# Glog_5G_V1.net
KiCad netlist of a schematic drawn in Altium Designer
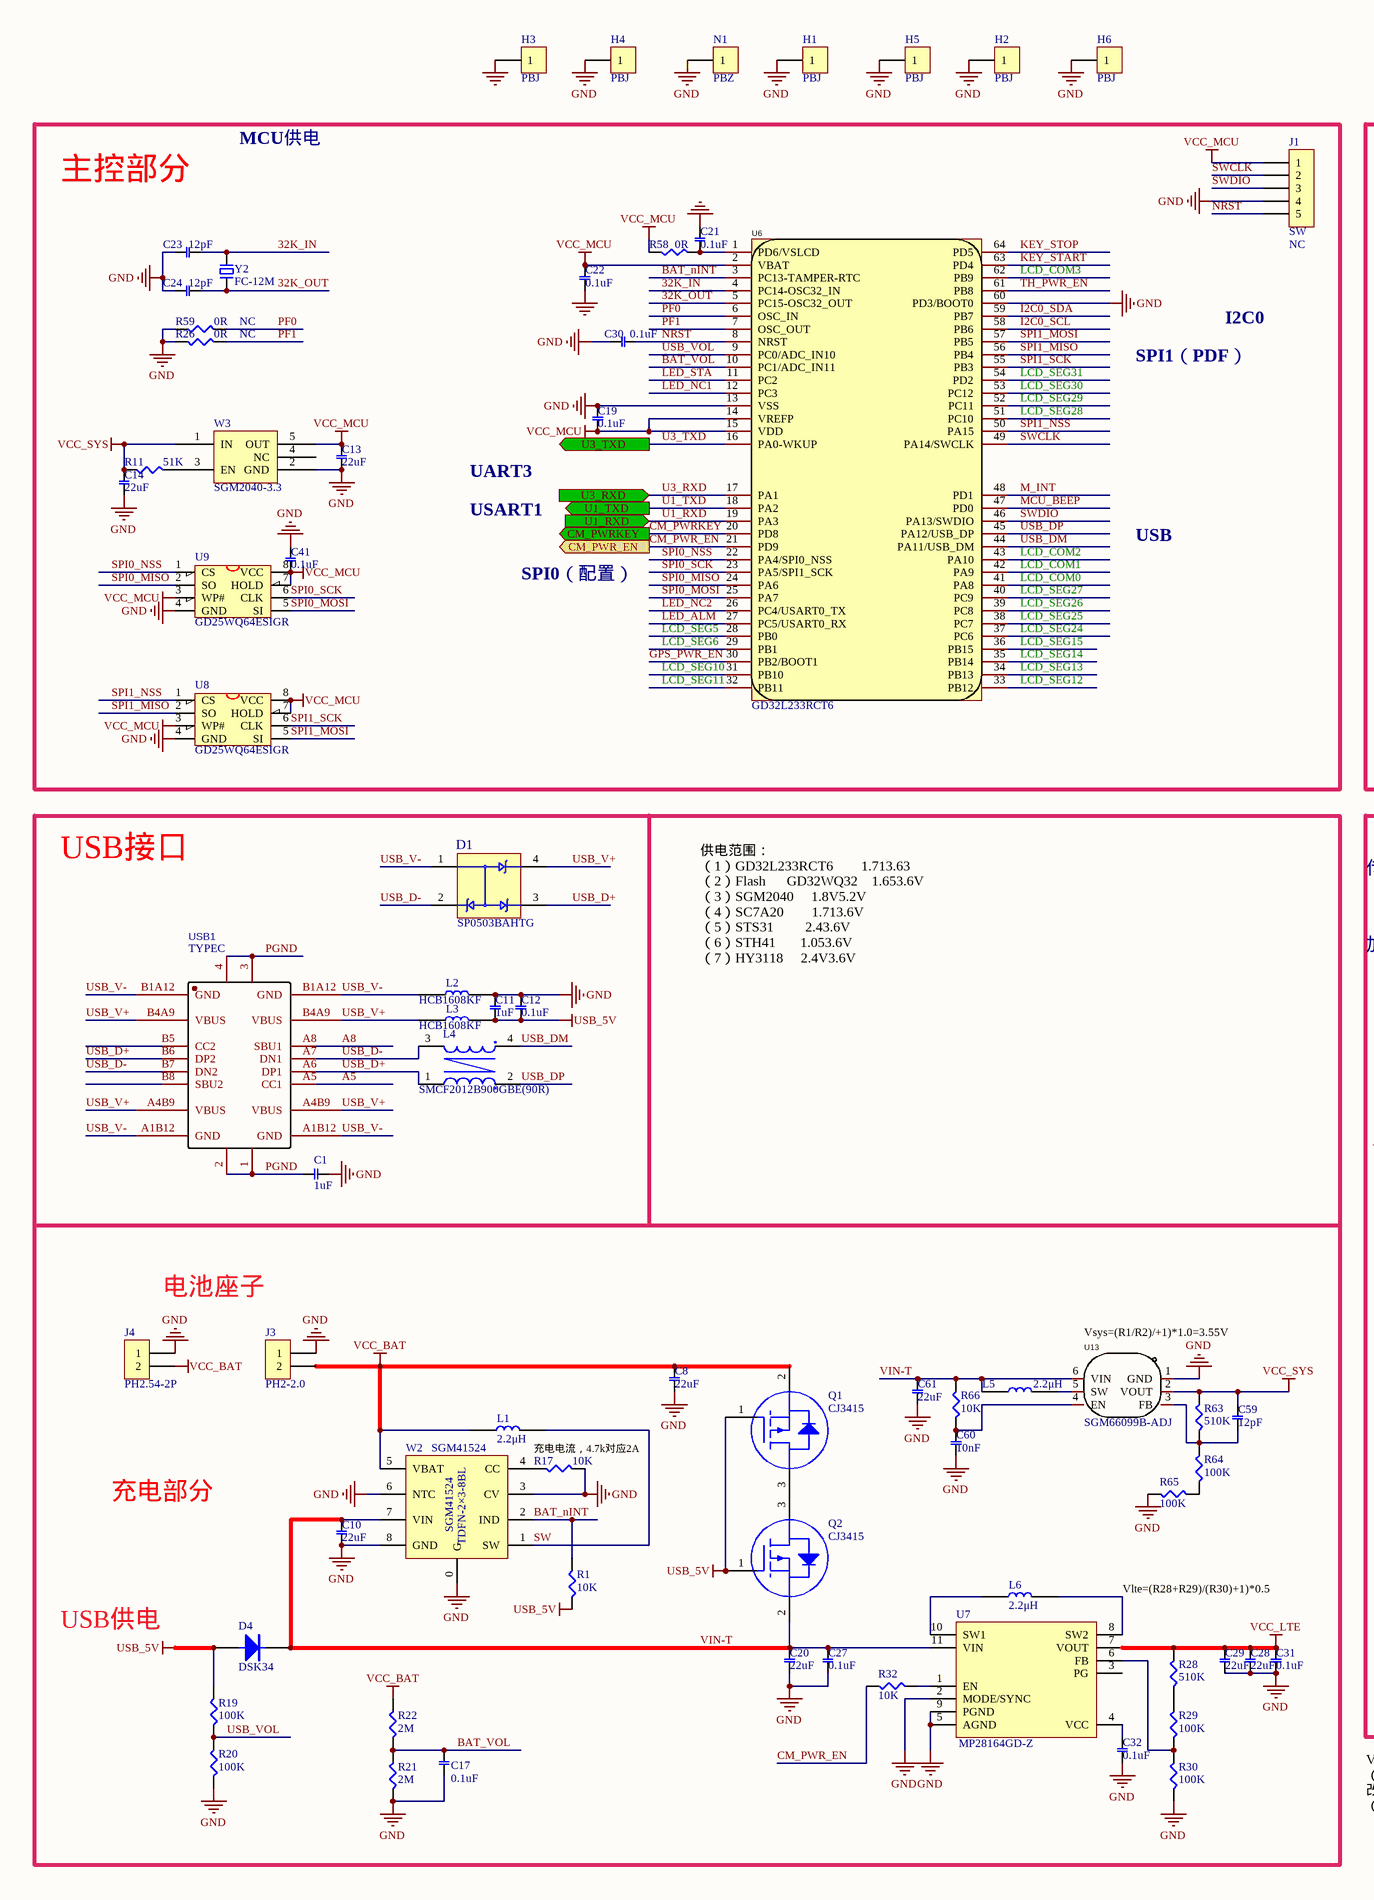
[diagram p0: Glog 5G_V1.SchDoc, left]
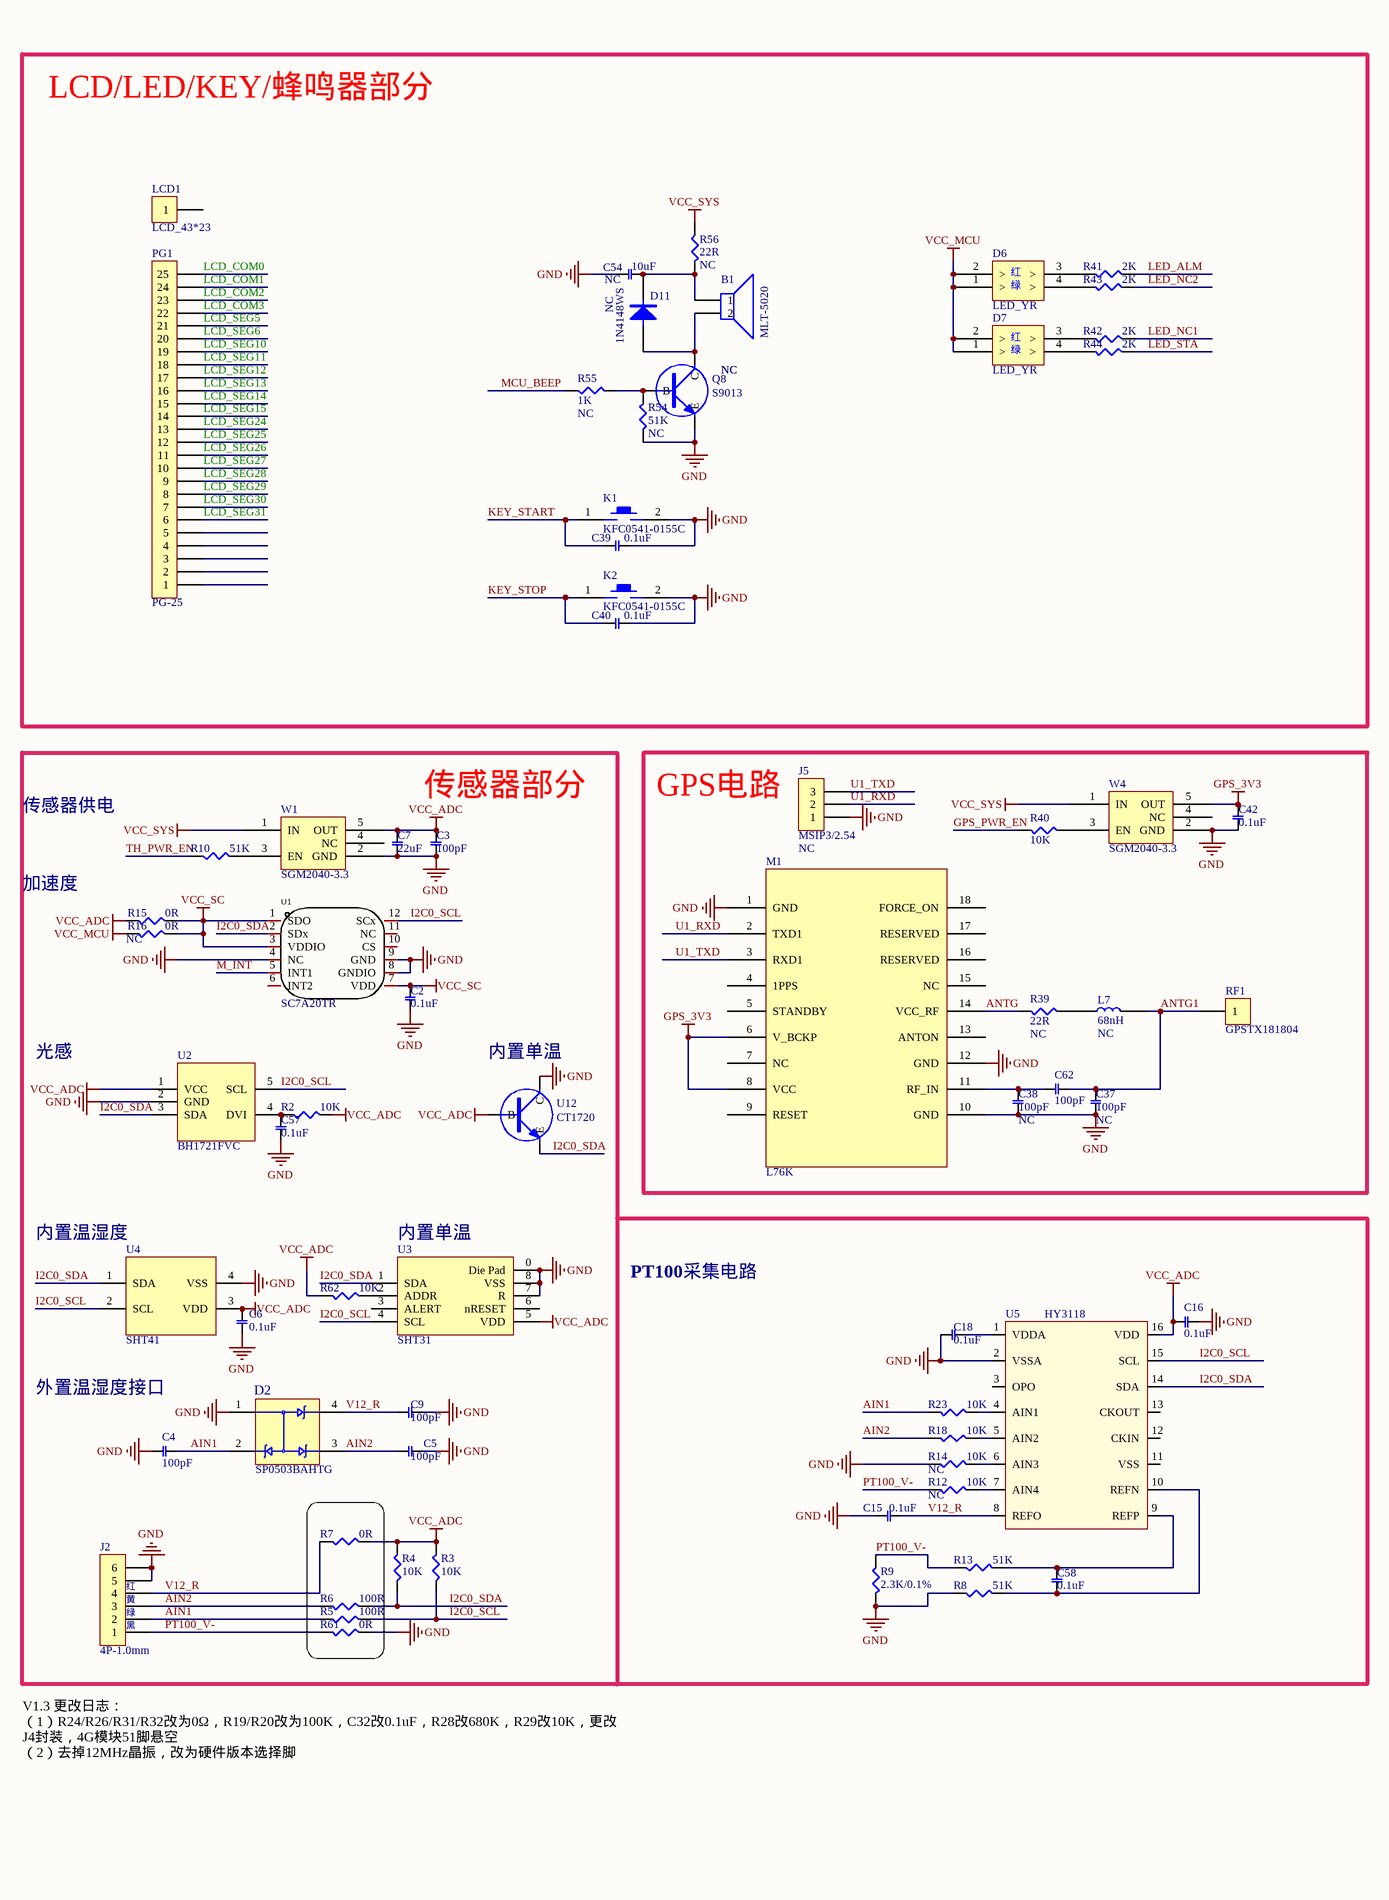
[diagram p1: Glog 5G_V1.SchDoc, right]

(export (version "E")
  (design (tool "Eeschema 10.0.6"))
  (components
    (comp (ref "B1")
      (value "MLT-5020")
      (footprint "MLT-5225")
      (fields (field (name "VALUES") "MLT-5020") (field (name "选焊") "NC"))
      (libsource (lib "JC_ERP_DB") (part "BUZZ"))
    )
    (comp (ref "C1")
      (value "1uF")
      (footprint "0402C")
      (fields (field (name "VALUES") "1uF"))
      (libsource (lib "JC_ERP_DB") (part "Capacity-CE"))
    )
    (comp (ref "C2")
      (value "0.1uF")
      (footprint "0402C")
      (fields (field (name "VALUES") "0.1uF"))
      (libsource (lib "JC_ERP_DB") (part "Capacity-CE"))
    )
    (comp (ref "C3")
      (value "100pF")
      (footprint "0402C")
      (fields (field (name "VALUES") "100pF"))
      (libsource (lib "JC_ERP_DB") (part "Capacity-CE"))
    )
    (comp (ref "C4")
      (value "100pF")
      (footprint "0402C")
      (fields (field (name "VALUES") "100pF"))
      (libsource (lib "JC_ERP_DB") (part "Capacity-CE"))
    )
    (comp (ref "C5")
      (value "100pF")
      (footprint "0402C")
      (fields (field (name "VALUES") "100pF"))
      (libsource (lib "JC_ERP_DB") (part "Capacity-CE"))
    )
    (comp (ref "C6")
      (value "0.1uF")
      (footprint "0402C")
      (fields (field (name "VALUES") "0.1uF"))
      (libsource (lib "JC_ERP_DB") (part "Capacity-CE"))
    )
    (comp (ref "C7")
      (value "22uF")
      (footprint "0603C")
      (fields (field (name "VALUES") "22uF"))
      (libsource (lib "JC_ERP_DB") (part "Capacity-CE"))
    )
    (comp (ref "C8")
      (value "22uF")
      (footprint "0603C")
      (fields (field (name "VALUES") "22uF"))
      (libsource (lib "JC_ERP_DB") (part "Capacity-CE"))
    )
    (comp (ref "C9")
      (value "100pF")
      (footprint "0402C")
      (fields (field (name "VALUES") "100pF"))
      (libsource (lib "JC_ERP_DB") (part "Capacity-CE"))
    )
    (comp (ref "C10")
      (value "22uF")
      (footprint "0603C")
      (fields (field (name "VALUES") "22uF"))
      (libsource (lib "JC_ERP_DB") (part "Capacity-CE"))
    )
    (comp (ref "C11")
      (value "1uF")
      (footprint "0402C")
      (fields (field (name "VALUES") "1uF"))
      (libsource (lib "JC_ERP_DB") (part "Capacity-CE"))
    )
    (comp (ref "C12")
      (value "0.1uF")
      (footprint "0402C")
      (fields (field (name "VALUES") "0.1uF"))
      (libsource (lib "JC_ERP_DB") (part "Capacity-CE"))
    )
    (comp (ref "C13")
      (value "22uF")
      (footprint "0603C")
      (fields (field (name "VALUES") "22uF"))
      (libsource (lib "JC_ERP_DB") (part "Capacity-CE"))
    )
    (comp (ref "C14")
      (value "22uF")
      (footprint "0603C")
      (fields (field (name "VALUES") "22uF"))
      (libsource (lib "JC_ERP_DB") (part "Capacity-CE"))
    )
    (comp (ref "C15")
      (value "0.1uF")
      (footprint "0402C")
      (fields (field (name "VALUES") "0.1uF"))
      (libsource (lib "JC_ERP_DB") (part "Capacity-CE"))
    )
    (comp (ref "C16")
      (value "0.1uF")
      (footprint "0402C")
      (fields (field (name "VALUES") "0.1uF"))
      (libsource (lib "JC_ERP_DB") (part "Capacity-CE"))
    )
    (comp (ref "C17")
      (value "0.1uF")
      (footprint "0402C")
      (fields (field (name "VALUES") "0.1uF"))
      (libsource (lib "JC_ERP_DB") (part "Capacity-CE"))
    )
    (comp (ref "C18")
      (value "0.1uF")
      (footprint "0402C")
      (fields (field (name "VALUES") "0.1uF"))
      (libsource (lib "JC_ERP_DB") (part "Capacity-CE"))
    )
    (comp (ref "C19")
      (value "0.1uF")
      (footprint "0402C")
      (fields (field (name "VALUES") "0.1uF"))
      (libsource (lib "JC_ERP_DB") (part "Capacity-CE"))
    )
    (comp (ref "C20")
      (value "22uF")
      (footprint "0603C")
      (fields (field (name "VALUES") "22uF"))
      (libsource (lib "JC_ERP_DB") (part "Capacity-CE"))
    )
    (comp (ref "C21")
      (value "0.1uF")
      (footprint "0402C")
      (fields (field (name "VALUES") "0.1uF"))
      (libsource (lib "JC_ERP_DB") (part "Capacity-CE"))
    )
    (comp (ref "C22")
      (value "0.1uF")
      (footprint "0402C")
      (fields (field (name "VALUES") "0.1uF"))
      (libsource (lib "JC_ERP_DB") (part "Capacity-CE"))
    )
    (comp (ref "C23")
      (value "12pF")
      (footprint "0402C")
      (fields (field (name "VALUES") "12pF"))
      (libsource (lib "JC_ERP_DB") (part "Capacity-CE"))
    )
    (comp (ref "C24")
      (value "12pF")
      (footprint "0402C")
      (fields (field (name "VALUES") "12pF"))
      (libsource (lib "JC_ERP_DB") (part "Capacity-CE"))
    )
    (comp (ref "C27")
      (value "0.1uF")
      (footprint "0402C")
      (fields (field (name "VALUES") "0.1uF"))
      (libsource (lib "JC_ERP_DB") (part "Capacity-CE"))
    )
    (comp (ref "C28")
      (value "22uF")
      (footprint "0603C")
      (fields (field (name "VALUES") "22uF"))
      (libsource (lib "JC_ERP_DB") (part "Capacity-CE"))
    )
    (comp (ref "C29")
      (value "22uF")
      (footprint "0603C")
      (fields (field (name "VALUES") "22uF"))
      (libsource (lib "JC_ERP_DB") (part "Capacity-CE"))
    )
    (comp (ref "C30")
      (value "0.1uF")
      (footprint "0402C")
      (fields (field (name "VALUES") "0.1uF"))
      (libsource (lib "JC_ERP_DB") (part "Capacity-CE"))
    )
    (comp (ref "C31")
      (value "0.1uF")
      (footprint "0402C")
      (fields (field (name "VALUES") "0.1uF"))
      (libsource (lib "JC_ERP_DB") (part "Capacity-CE"))
    )
    (comp (ref "C32")
      (value "0.1uF")
      (footprint "0402C")
      (fields (field (name "VALUES") "0.1uF"))
      (libsource (lib "JC_ERP_DB") (part "Capacity-CE"))
    )
    (comp (ref "C37")
      (value "100pF")
      (footprint "0402C")
      (fields (field (name "VALUES") "100pF") (field (name "选焊") "NC"))
      (libsource (lib "JC_ERP_DB") (part "Capacity-CE"))
    )
    (comp (ref "C38")
      (value "100pF")
      (footprint "0402C")
      (fields (field (name "VALUES") "100pF") (field (name "选焊") "NC"))
      (libsource (lib "JC_ERP_DB") (part "Capacity-CE"))
    )
    (comp (ref "C39")
      (value "0.1uF")
      (footprint "0402C")
      (fields (field (name "VALUES") "0.1uF"))
      (libsource (lib "JC_ERP_DB") (part "Capacity-CE"))
    )
    (comp (ref "C40")
      (value "0.1uF")
      (footprint "0402C")
      (fields (field (name "VALUES") "0.1uF"))
      (libsource (lib "JC_ERP_DB") (part "Capacity-CE"))
    )
    (comp (ref "C41")
      (value "0.1uF")
      (footprint "0402C")
      (fields (field (name "VALUES") "0.1uF"))
      (libsource (lib "JC_ERP_DB") (part "Capacity-CE"))
    )
    (comp (ref "C42")
      (value "0.1uF")
      (footprint "0402C")
      (fields (field (name "VALUES") "0.1uF"))
      (libsource (lib "JC_ERP_DB") (part "Capacity-CE"))
    )
    (comp (ref "C54")
      (value "10uF")
      (footprint "0603C")
      (fields (field (name "VALUES") "10uF") (field (name "选焊") "NC"))
      (libsource (lib "JC_ERP_DB") (part "Capacity-CE"))
    )
    (comp (ref "C57")
      (value "0.1uF")
      (footprint "0402C")
      (fields (field (name "VALUES") "0.1uF"))
      (libsource (lib "JC_ERP_DB") (part "Capacity-CE"))
    )
    (comp (ref "C58")
      (value "0.1uF")
      (footprint "0402C")
      (fields (field (name "VALUES") "0.1uF"))
      (libsource (lib "JC_ERP_DB") (part "Capacity-CE"))
    )
    (comp (ref "C59")
      (value "12pF")
      (footprint "0402C")
      (fields (field (name "VALUES") "12pF"))
      (libsource (lib "JC_ERP_DB") (part "Capacity-CE"))
    )
    (comp (ref "C60")
      (value "10nF")
      (footprint "0402C")
      (fields (field (name "VALUES") "10nF"))
      (libsource (lib "JC_ERP_DB") (part "Capacity-CE"))
    )
    (comp (ref "C61")
      (value "22uF")
      (footprint "0603C")
      (fields (field (name "VALUES") "22uF"))
      (libsource (lib "JC_ERP_DB") (part "Capacity-CE"))
    )
    (comp (ref "C62")
      (value "100pF")
      (footprint "0402C")
      (fields (field (name "VALUES") "100pF"))
      (libsource (lib "JC_ERP_DB") (part "Capacity-CE"))
    )
    (comp (ref "D1")
      (value "SP0503BAHTG")
      (footprint "SP0503")
      (fields (field (name "VALUES") "SP0503BAHTG"))
      (libsource (lib "JC_ERP_DB") (part "SP0503BATH"))
    )
    (comp (ref "D2")
      (value "SP0503BAHTG")
      (footprint "SP0503")
      (fields (field (name "VALUES") "SP0503BAHTG"))
      (libsource (lib "JC_ERP_DB") (part "SP0503BATH"))
    )
    (comp (ref "D4")
      (value "DSK34")
      (footprint "SOD-123FL")
      (fields (field (name "VALUES") "DSK34"))
      (libsource (lib "JC_ERP_DB") (part "Diode"))
    )
    (comp (ref "D6")
      (value "LED_YR")
      (footprint "TWO_LED_2COL_0805")
      (fields (field (name "VALUES") "LED_YR"))
      (libsource (lib "JC_ERP_DB") (part "0805-D-LED"))
    )
    (comp (ref "D7")
      (value "LED_YR")
      (footprint "TWO_LED_2COL_0805")
      (fields (field (name "VALUES") "LED_YR"))
      (libsource (lib "JC_ERP_DB") (part "0805-D-LED"))
    )
    (comp (ref "D11")
      (value "1N4148WS")
      (footprint "SOD123")
      (fields (field (name "VALUES") "1N4148WS") (field (name "选焊") "NC"))
      (libsource (lib "JC_ERP_DB") (part "Diode"))
    )
    (comp (ref "H1")
      (value "PBJ")
      (footprint "PBZJZ")
      (fields (field (name "VALUES") "PBJ"))
      (libsource (lib "JC_ERP_DB") (part "CON1P"))
    )
    (comp (ref "H2")
      (value "PBJ")
      (footprint "PBZJZ")
      (fields (field (name "VALUES") "PBJ"))
      (libsource (lib "JC_ERP_DB") (part "CON1P"))
    )
    (comp (ref "H3")
      (value "PBJ")
      (footprint "PBZJZ")
      (fields (field (name "VALUES") "PBJ"))
      (libsource (lib "JC_ERP_DB") (part "CON1P"))
    )
    (comp (ref "H4")
      (value "PBJ")
      (footprint "PBZJZ")
      (fields (field (name "VALUES") "PBJ"))
      (libsource (lib "JC_ERP_DB") (part "CON1P"))
    )
    (comp (ref "H5")
      (value "PBJ")
      (footprint "PBZJZ")
      (fields (field (name "VALUES") "PBJ"))
      (libsource (lib "JC_ERP_DB") (part "CON1P"))
    )
    (comp (ref "H6")
      (value "PBJ")
      (footprint "PBZJZ")
      (fields (field (name "VALUES") "PBJ"))
      (libsource (lib "JC_ERP_DB") (part "CON1P"))
    )
    (comp (ref "J1")
      (value "SW")
      (footprint "HDR1X5")
      (description "Connector")
      (fields (field (name "选焊") "NC"))
      (libsource (lib "Integrated Devices") (part "CON5"))
    )
    (comp (ref "J2")
      (value "4P-1.0mm")
      (footprint "SH1.0MM-4P")
      (fields (field (name "VALUES") "4P-1.0mm"))
      (libsource (lib "JC_ERP_DB") (part "CON-1*6PIN"))
    )
    (comp (ref "J3")
      (value "PH2-2.0")
      (footprint "smd2 dh2")
      (fields (field (name "VALUES") "PH2-2.0"))
      (libsource (lib "JC_ERP_DB") (part "CON-1*2PIN"))
    )
    (comp (ref "J4")
      (value "PH2.54-2P")
      (footprint "SMD_DH2.54_L")
      (fields (field (name "VALUES") "PH2.54-2P"))
      (libsource (lib "JC_ERP_DB") (part "CON-1*2PIN"))
    )
    (comp (ref "J5")
      (value "MSIP3/2.54")
      (footprint "SIP-3(2.54MM)")
      (fields (field (name "VALUES") "MSIP3/2.54") (field (name "选焊") "NC"))
      (libsource (lib "ERP_DB") (part "CON-1*3PIN"))
    )
    (comp (ref "K1")
      (value "KFC0541-0155C")
      (footprint "KEY-0505")
      (fields (field (name "VALUES") "KFC0541-0155C"))
      (libsource (lib "JC_ERP_DB") (part "KEY_M"))
    )
    (comp (ref "K2")
      (value "KFC0541-0155C")
      (footprint "KEY-0505")
      (fields (field (name "VALUES") "KFC0541-0155C"))
      (libsource (lib "JC_ERP_DB") (part "KEY_M"))
    )
    (comp (ref "L1")
      (value "2.2μH")
      (footprint "SMD-4020")
      (fields (field (name "VALUES") "2.2μH"))
      (libsource (lib "JC_ERP_DB") (part "Inductor-SMT-2PIN"))
    )
    (comp (ref "L2")
      (value "HCB1608KF")
      (footprint "0805L")
      (fields (field (name "VALUES") "HCB1608KF"))
      (libsource (lib "JC_ERP_DB") (part "Inductor-SMT-2PIN"))
    )
    (comp (ref "L3")
      (value "HCB1608KF")
      (footprint "0805L")
      (fields (field (name "VALUES") "HCB1608KF"))
      (libsource (lib "JC_ERP_DB") (part "Inductor-SMT-2PIN"))
    )
    (comp (ref "L4")
      (value "SMCF2012B900GBE(90R)")
      (footprint "SMCF2012")
      (fields (field (name "VALUES") "SMCF2012B900GBE(90R)"))
      (libsource (lib "JC_ERP_DB") (part "Inductor-CM"))
    )
    (comp (ref "L5")
      (value "2.2μH")
      (footprint "SMD-4020")
      (fields (field (name "VALUES") "2.2μH"))
      (libsource (lib "JC_ERP_DB") (part "Inductor-SMT-2PIN"))
    )
    (comp (ref "L6")
      (value "2.2μH")
      (footprint "SMD-4020")
      (fields (field (name "VALUES") "2.2μH"))
      (libsource (lib "JC_ERP_DB") (part "Inductor-SMT-2PIN"))
    )
    (comp (ref "L7")
      (value "68nH")
      (footprint "0603L")
      (fields (field (name "VALUES") "68nH") (field (name "选焊") "NC"))
      (libsource (lib "JC_ERP_DB") (part "Inductor-SMT-2PIN"))
    )
    (comp (ref "LCD1")
      (value "LCD_43*23")
      (footprint "LCD_43*23*2.8")
      (fields (field (name "VALUES") "LCD_43*23"))
      (libsource (lib "") (part "CON1P_1"))
    )
    (comp (ref "M1")
      (value "L76K")
      (footprint "L76CGPS")
      (fields (field (name "VALUES") "L76K"))
      (libsource (lib "JC_ERP_DB") (part "L76CGPS"))
    )
    (comp (ref "N1")
      (value "PBZ")
      (footprint "PBZ_36*28mm")
      (fields (field (name "VALUES") "PBZ"))
      (libsource (lib "JC_ERP_DB") (part "CON1P"))
    )
    (comp (ref "PG1")
      (value "PG-25")
      (footprint "PG25-L46*W2*H3mm")
      (fields (field (name "VALUES") "PG-25"))
      (libsource (lib "JC_ERP_DB") (part "CON-1*25PIN"))
    )
    (comp (ref "Q1")
      (value "CJ3415")
      (footprint "SOT-23-MOS")
      (fields (field (name "VALUES") "CJ3415"))
      (libsource (lib "") (part "MOS-P-Z_1"))
    )
    (comp (ref "Q2")
      (value "CJ3415")
      (footprint "SOT-23-MOS")
      (fields (field (name "VALUES") "CJ3415"))
      (libsource (lib "JC_ERP_DB") (part "MOS-P-Z"))
    )
    (comp (ref "Q8")
      (value "S9013")
      (footprint "SOT23-N")
      (fields (field (name "VALUES") "S9013") (field (name "选焊") "NC"))
      (libsource (lib "JC_ERP_DB") (part "Dynatron-NPN"))
    )
    (comp (ref "R1")
      (value "10K")
      (footprint "0402R")
      (fields (field (name "VALUES") "10K"))
      (libsource (lib "JC_ERP_DB") (part "Resistors-SMT"))
    )
    (comp (ref "R2")
      (value "10K")
      (footprint "0402R")
      (fields (field (name "VALUES") "10K"))
      (libsource (lib "JC_ERP_DB") (part "Resistors-SMT"))
    )
    (comp (ref "R3")
      (value "10K")
      (footprint "0402R")
      (fields (field (name "VALUES") "10K"))
      (libsource (lib "JC_ERP_DB") (part "Resistors-SMT"))
    )
    (comp (ref "R4")
      (value "10K")
      (footprint "0402R")
      (fields (field (name "VALUES") "10K"))
      (libsource (lib "JC_ERP_DB") (part "Resistors-SMT"))
    )
    (comp (ref "R5")
      (value "100R")
      (footprint "0402R")
      (fields (field (name "VALUES") "100R"))
      (libsource (lib "JC_ERP_DB") (part "Resistors-SMT"))
    )
    (comp (ref "R6")
      (value "100R")
      (footprint "0402R")
      (fields (field (name "VALUES") "100R"))
      (libsource (lib "JC_ERP_DB") (part "Resistors-SMT"))
    )
    (comp (ref "R7")
      (value "0R")
      (footprint "0402R")
      (fields (field (name "VALUES") "0R"))
      (libsource (lib "JC_ERP_DB") (part "Resistors-SMT"))
    )
    (comp (ref "R8")
      (value "51K")
      (footprint "0402R")
      (fields (field (name "VALUES") "51K"))
      (libsource (lib "JC_ERP_DB") (part "Resistors-SMT"))
    )
    (comp (ref "R9")
      (value "2.3K/0.1%")
      (footprint "1206R")
      (fields (field (name "VALUES") "2.3K/0.1%"))
      (libsource (lib "JC_ERP_DB") (part "Resistors-SMT"))
    )
    (comp (ref "R10")
      (value "51K")
      (footprint "0402R")
      (fields (field (name "VALUES") "51K"))
      (libsource (lib "JC_ERP_DB") (part "Resistors-SMT"))
    )
    (comp (ref "R11")
      (value "51K")
      (footprint "0402R")
      (fields (field (name "VALUES") "51K"))
      (libsource (lib "JC_ERP_DB") (part "Resistors-SMT"))
    )
    (comp (ref "R12")
      (value "10K")
      (footprint "0402R")
      (fields (field (name "VALUES") "10K") (field (name "选焊") "NC"))
      (libsource (lib "JC_ERP_DB") (part "Resistors-SMT"))
    )
    (comp (ref "R13")
      (value "51K")
      (footprint "0402R")
      (fields (field (name "VALUES") "51K"))
      (libsource (lib "JC_ERP_DB") (part "Resistors-SMT"))
    )
    (comp (ref "R14")
      (value "10K")
      (footprint "0402R")
      (fields (field (name "VALUES") "10K") (field (name "选焊") "NC"))
      (libsource (lib "JC_ERP_DB") (part "Resistors-SMT"))
    )
    (comp (ref "R15")
      (value "0R")
      (footprint "0402R")
      (fields (field (name "VALUES") "0R"))
      (libsource (lib "JC_ERP_DB") (part "Resistors-SMT"))
    )
    (comp (ref "R16")
      (value "0R")
      (footprint "0402R")
      (fields (field (name "VALUES") "0R") (field (name "选焊") "NC"))
      (libsource (lib "JC_ERP_DB") (part "Resistors-SMT"))
    )
    (comp (ref "R17")
      (value "10K")
      (footprint "0402R")
      (fields (field (name "VALUES") "10K"))
      (libsource (lib "JC_ERP_DB") (part "Resistors-SMT"))
    )
    (comp (ref "R18")
      (value "10K")
      (footprint "0402R")
      (fields (field (name "VALUES") "10K"))
      (libsource (lib "JC_ERP_DB") (part "Resistors-SMT"))
    )
    (comp (ref "R19")
      (value "100K")
      (footprint "0402R")
      (fields (field (name "VALUES") "100K"))
      (libsource (lib "JC_ERP_DB") (part "Resistors-SMT"))
    )
    (comp (ref "R20")
      (value "100K")
      (footprint "0402R")
      (fields (field (name "VALUES") "100K"))
      (libsource (lib "JC_ERP_DB") (part "Resistors-SMT"))
    )
    (comp (ref "R21")
      (value "2M")
      (footprint "0402R")
      (fields (field (name "VALUES") "2M"))
      (libsource (lib "JC_ERP_DB") (part "Resistors-SMT"))
    )
    (comp (ref "R22")
      (value "2M")
      (footprint "0402R")
      (fields (field (name "VALUES") "2M"))
      (libsource (lib "JC_ERP_DB") (part "Resistors-SMT"))
    )
    (comp (ref "R23")
      (value "10K")
      (footprint "0402R")
      (fields (field (name "VALUES") "10K"))
      (libsource (lib "JC_ERP_DB") (part "Resistors-SMT"))
    )
    (comp (ref "R26")
      (value "0R")
      (footprint "0402R")
      (fields (field (name "VALUES") "0R") (field (name "选焊") "NC"))
      (libsource (lib "JC_ERP_DB") (part "Resistors-SMT"))
    )
    (comp (ref "R28")
      (value "510K")
      (footprint "0603R")
      (fields (field (name "VALUES") "510K"))
      (libsource (lib "JC_ERP_DB") (part "Resistors-SMT"))
    )
    (comp (ref "R29")
      (value "100K")
      (footprint "0402R")
      (fields (field (name "VALUES") "100K"))
      (libsource (lib "JC_ERP_DB") (part "Resistors-SMT"))
    )
    (comp (ref "R30")
      (value "100K")
      (footprint "0402R")
      (fields (field (name "VALUES") "100K"))
      (libsource (lib "JC_ERP_DB") (part "Resistors-SMT"))
    )
    (comp (ref "R32")
      (value "10K")
      (footprint "0402R")
      (fields (field (name "VALUES") "10K"))
      (libsource (lib "JC_ERP_DB") (part "Resistors-SMT"))
    )
    (comp (ref "R39")
      (value "22R")
      (footprint "0402R")
      (fields (field (name "VALUES") "22R") (field (name "选焊") "NC"))
      (libsource (lib "JC_ERP_DB") (part "Resistors-SMT"))
    )
    (comp (ref "R40")
      (value "10K")
      (footprint "0402R")
      (fields (field (name "VALUES") "10K"))
      (libsource (lib "JC_ERP_DB") (part "Resistors-SMT"))
    )
    (comp (ref "R41")
      (value "2K")
      (footprint "0402R")
      (fields (field (name "VALUES") "2K"))
      (libsource (lib "JC_ERP_DB") (part "Resistors-SMT"))
    )
    (comp (ref "R42")
      (value "2K")
      (footprint "0402R")
      (fields (field (name "VALUES") "2K"))
      (libsource (lib "JC_ERP_DB") (part "Resistors-SMT"))
    )
    (comp (ref "R43")
      (value "2K")
      (footprint "0402R")
      (fields (field (name "VALUES") "2K"))
      (libsource (lib "JC_ERP_DB") (part "Resistors-SMT"))
    )
    (comp (ref "R44")
      (value "2K")
      (footprint "0402R")
      (fields (field (name "VALUES") "2K"))
      (libsource (lib "JC_ERP_DB") (part "Resistors-SMT"))
    )
    (comp (ref "R54")
      (value "51K")
      (footprint "0402R")
      (fields (field (name "VALUES") "51K") (field (name "选焊") "NC"))
      (libsource (lib "JC_ERP_DB") (part "Resistors-SMT"))
    )
    (comp (ref "R55")
      (value "1K")
      (footprint "0402R")
      (fields (field (name "VALUES") "1K") (field (name "选焊") "NC"))
      (libsource (lib "JC_ERP_DB") (part "Resistors-SMT"))
    )
    (comp (ref "R56")
      (value "22R")
      (footprint "0402R")
      (fields (field (name "VALUES") "22R") (field (name "选焊") "NC"))
      (libsource (lib "JC_ERP_DB") (part "Resistors-SMT"))
    )
    (comp (ref "R58")
      (value "0R")
      (footprint "0402R")
      (fields (field (name "VALUES") "0R"))
      (libsource (lib "JC_ERP_DB") (part "Resistors-SMT"))
    )
    (comp (ref "R59")
      (value "0R")
      (footprint "0402R")
      (fields (field (name "VALUES") "0R") (field (name "选焊") "NC"))
      (libsource (lib "JC_ERP_DB") (part "Resistors-SMT"))
    )
    (comp (ref "R61")
      (value "0R")
      (footprint "0402R")
      (fields (field (name "VALUES") "0R"))
      (libsource (lib "JC_ERP_DB") (part "Resistors-SMT"))
    )
    (comp (ref "R62")
      (value "10K")
      (footprint "0402R")
      (fields (field (name "VALUES") "10K"))
      (libsource (lib "JC_ERP_DB") (part "Resistors-SMT"))
    )
    (comp (ref "R63")
      (value "510K")
      (footprint "0603R")
      (fields (field (name "VALUES") "510K"))
      (libsource (lib "JC_ERP_DB") (part "Resistors-SMT"))
    )
    (comp (ref "R64")
      (value "100K")
      (footprint "0402R")
      (fields (field (name "VALUES") "100K"))
      (libsource (lib "JC_ERP_DB") (part "Resistors-SMT"))
    )
    (comp (ref "R65")
      (value "100K")
      (footprint "0402R")
      (fields (field (name "VALUES") "100K"))
      (libsource (lib "JC_ERP_DB") (part "Resistors-SMT"))
    )
    (comp (ref "R66")
      (value "10K")
      (footprint "0402R")
      (fields (field (name "VALUES") "10K"))
      (libsource (lib "JC_ERP_DB") (part "Resistors-SMT"))
    )
    (comp (ref "RF1")
      (value "GPSTX181804")
      (footprint "GPSTX_18*18*4mm")
      (fields (field (name "VALUES") "GPSTX181804"))
      (libsource (lib "JC_ERP_DB") (part "CON1P"))
    )
    (comp (ref "U1")
      (value "SC7A20TR")
      (footprint "LGA-12_L2.0-W2.0-P0.50-BL")
      (fields (field (name "VALUES") "SC7A20TR"))
      (libsource (lib "JC_ERP_DB") (part "SC7A20TR"))
    )
    (comp (ref "U2")
      (value "BH1721FVC")
      (footprint "BH1721FVC")
      (fields (field (name "VALUES") "BH1721FVC"))
      (libsource (lib "JC_ERP_DB") (part "BH1721FVC"))
    )
    (comp (ref "U3")
      (value "SHT31")
      (footprint "SHT3X")
      (fields (field (name "VALUES") "SHT31"))
      (libsource (lib "JC_ERP_DB") (part "SHT3X"))
    )
    (comp (ref "U4")
      (value "SHT41")
      (footprint "SHT4X")
      (fields (field (name "VALUES") "SHT41"))
      (libsource (lib "JC_ERP_DB") (part "SHT4X"))
    )
    (comp (ref "U5")
      (value "HY3118")
      (footprint "TSSOP16")
      (fields (field (name "VALUES") "HY3118"))
      (libsource (lib "JC_ERP_DB") (part "HY3118"))
    )
    (comp (ref "U6")
      (value "GD32L233RCT6")
      (footprint "LQFP-64")
      (fields (field (name "VALUES") "GD32L233RCT6"))
      (libsource (lib "JC_ERP_DB") (part "GD32L233Rx"))
    )
    (comp (ref "U7")
      (value "MP28164GD-Z")
      (footprint "QFN11")
      (fields (field (name "VALUES") "MP28164GD-Z"))
      (libsource (lib "JC_ERP_DB") (part "MP28164"))
    )
    (comp (ref "U8")
      (value "GD25WQ64ESIGR")
      (footprint "SOP8")
      (description "xx25X16_32")
      (fields (field (name "VALUES") "GD25WQ64ESIGR"))
      (libsource (lib "JC_ERP_DB") (part "W25X16"))
    )
    (comp (ref "U9")
      (value "GD25WQ64ESIGR")
      (footprint "SOP8")
      (description "xx25X16_32")
      (fields (field (name "VALUES") "GD25WQ64ESIGR"))
      (libsource (lib "JC_ERP_DB") (part "W25X16"))
    )
    (comp (ref "U12")
      (value "CT1720")
      (footprint "SOT23-N")
      (fields (field (name "VALUES") "CT1720"))
      (libsource (lib "JC_ERP_DB") (part "Dynatron-NPN"))
    )
    (comp (ref "U13")
      (value "SGM66099B-ADJ")
      (footprint "TDFN-6_L2.0-W2.0-P0.65-BL-EP")
      (fields (field (name "VALUES") "SGM66099B-ADJ"))
      (libsource (lib "JC_ERP_DB") (part "SGM66099B-ADJYT/TR"))
    )
    (comp (ref "USB1")
      (value "TYPEC")
      (footprint "USB-TypeC")
      (fields (field (name "VALUES") "TYPEC"))
      (libsource (lib "JC_ERP_DB") (part "USB-TYPEC"))
    )
    (comp (ref "W1")
      (value "SGM2040-3.3")
      (footprint "SOT23-5")
      (fields (field (name "VALUES") "SGM2040-3.3"))
      (libsource (lib "JC_ERP_DB") (part "SGM2040"))
    )
    (comp (ref "W2")
      (value "SGM41524")
      (footprint "SGM41524")
      (fields (field (name "VALUES") "SGM41524"))
      (libsource (lib "JC_ERP_DB") (part "SGM41524"))
    )
    (comp (ref "W3")
      (value "SGM2040-3.3")
      (footprint "SOT23-5")
      (fields (field (name "VALUES") "SGM2040-3.3"))
      (libsource (lib "JC_ERP_DB") (part "SGM2040"))
    )
    (comp (ref "W4")
      (value "SGM2040-3.3")
      (footprint "SOT23-5")
      (fields (field (name "VALUES") "SGM2040-3.3"))
      (libsource (lib "JC_ERP_DB") (part "SGM2040"))
    )
    (comp (ref "Y2")
      (value "FC-12M")
      (footprint "XTAL_2012")
      (fields (field (name "VALUES") "FC-12M"))
      (libsource (lib "JC_ERP_DB") (part "Crystal"))
    )
  )
  (nets
    (net (code "1") (name "/32K_IN") (class "Default")
      (node (ref "C23") (pin "2") (pintype "passive"))
      (node (ref "U6") (pin "4") (pinfunction "PC14-OSC32_IN_4") (pintype "passive"))
      (node (ref "Y2") (pin "2") (pinfunction "2_2") (pintype "passive"))
    )
    (net (code "2") (name "/32K_OUT") (class "Default")
      (node (ref "C24") (pin "2") (pintype "passive"))
      (node (ref "U6") (pin "5") (pinfunction "PC15-OSC32_OUT_5") (pintype "passive"))
      (node (ref "Y2") (pin "1") (pinfunction "1_1") (pintype "passive"))
    )
    (net (code "3") (name "/A5") (class "Default")
      (node (ref "USB1") (pin "A5") (pinfunction "CC1_A5") (pintype "passive"))
    )
    (net (code "4") (name "/A8") (class "Default")
      (node (ref "USB1") (pin "A8") (pinfunction "SBU1_A8") (pintype "passive"))
    )
    (net (code "5") (name "/AIN1") (class "Default")
      (node (ref "C4") (pin "1") (pintype "passive"))
      (node (ref "D2") (pin "2") (pintype "passive"))
      (node (ref "J2") (pin "2") (pinfunction "2_2") (pintype "passive"))
      (node (ref "R23") (pin "2") (pinfunction "2_2") (pintype "passive"))
      (node (ref "R5") (pin "2") (pinfunction "2_2") (pintype "passive"))
    )
    (net (code "6") (name "/AIN2") (class "Default")
      (node (ref "C5") (pin "2") (pintype "passive"))
      (node (ref "D2") (pin "3") (pintype "passive"))
      (node (ref "J2") (pin "3") (pinfunction "3_3") (pintype "passive"))
      (node (ref "R18") (pin "2") (pinfunction "2_2") (pintype "passive"))
      (node (ref "R6") (pin "2") (pinfunction "2_2") (pintype "passive"))
    )
    (net (code "7") (name "/ANTG") (class "Default")
      (node (ref "M1") (pin "14") (pinfunction "VCC_RF_14") (pintype "passive"))
      (node (ref "R39") (pin "1") (pinfunction "1_1") (pintype "passive"))
    )
    (net (code "8") (name "/ANTG1") (class "Default")
      (node (ref "C37") (pin "1") (pintype "passive"))
      (node (ref "C62") (pin "2") (pintype "passive"))
      (node (ref "L7") (pin "2") (pinfunction "2_2") (pintype "passive"))
      (node (ref "RF1") (pin "1") (pinfunction "1_1") (pintype "passive"))
    )
    (net (code "9") (name "/BAT_VOL") (class "Default")
      (node (ref "C17") (pin "1") (pintype "passive"))
      (node (ref "R21") (pin "2") (pinfunction "2_2") (pintype "passive"))
      (node (ref "R22") (pin "1") (pinfunction "1_1") (pintype "passive"))
      (node (ref "U6") (pin "10") (pinfunction "PC1/ADC_IN11_10") (pintype "passive"))
    )
    (net (code "10") (name "/BAT_nINT") (class "Default")
      (node (ref "R1") (pin "2") (pinfunction "2_2") (pintype "passive"))
      (node (ref "U6") (pin "3") (pinfunction "PC13-TAMPER-RTC_3") (pintype "passive"))
      (node (ref "W2") (pin "2") (pinfunction "IND_2") (pintype "passive"))
    )
    (net (code "11") (name "/CM_PWRKEY") (class "Default")
      (node (ref "U6") (pin "20") (pinfunction "PD8_20") (pintype "passive"))
    )
    (net (code "12") (name "/CM_PWR_EN") (class "Default")
      (node (ref "R32") (pin "2") (pinfunction "2_2") (pintype "passive"))
      (node (ref "U6") (pin "21") (pinfunction "PD9_21") (pintype "passive"))
    )
    (net (code "13") (name "/GPS_PWR_EN") (class "Default")
      (node (ref "R40") (pin "2") (pinfunction "2_2") (pintype "passive"))
      (node (ref "U6") (pin "30") (pinfunction "PB2/BOOT1_30") (pintype "passive"))
    )
    (net (code "14") (name "/I2C0_SCL") (class "Default")
      (node (ref "R3") (pin "1") (pinfunction "1_1") (pintype "passive"))
      (node (ref "R5") (pin "1") (pinfunction "1_1") (pintype "passive"))
      (node (ref "U1") (pin "12") (pinfunction "SCx_12") (pintype "passive"))
      (node (ref "U2") (pin "5") (pinfunction "SCL_5") (pintype "passive"))
      (node (ref "U3") (pin "4") (pinfunction "SCL_4") (pintype "passive"))
      (node (ref "U4") (pin "2") (pinfunction "SCL_2") (pintype "passive"))
      (node (ref "U5") (pin "15") (pinfunction "SCL_15") (pintype "passive"))
      (node (ref "U6") (pin "58") (pinfunction "PB6_58") (pintype "passive"))
    )
    (net (code "15") (name "/I2C0_SDA") (class "Default")
      (node (ref "R4") (pin "1") (pinfunction "1_1") (pintype "passive"))
      (node (ref "R6") (pin "1") (pinfunction "1_1") (pintype "passive"))
      (node (ref "U1") (pin "2") (pinfunction "SDx_2") (pintype "passive"))
      (node (ref "U12") (pin "E") (pinfunction "E_E") (pintype "passive"))
      (node (ref "U2") (pin "3") (pinfunction "SDA_3") (pintype "passive"))
      (node (ref "U3") (pin "1") (pinfunction "SDA_1") (pintype "passive"))
      (node (ref "U4") (pin "1") (pinfunction "SDA_1") (pintype "passive"))
      (node (ref "U5") (pin "14") (pinfunction "SDA_14") (pintype "passive"))
      (node (ref "U6") (pin "59") (pinfunction "PB7_59") (pintype "passive"))
    )
    (net (code "16") (name "/KEY_START") (class "Default")
      (node (ref "C39") (pin "2") (pintype "passive"))
      (node (ref "K1") (pin "1") (pinfunction "1_1") (pintype "passive"))
      (node (ref "U6") (pin "63") (pinfunction "PD4_63") (pintype "passive"))
    )
    (net (code "17") (name "/KEY_STOP") (class "Default")
      (node (ref "C40") (pin "2") (pintype "passive"))
      (node (ref "K2") (pin "1") (pinfunction "1_1") (pintype "passive"))
      (node (ref "U6") (pin "64") (pinfunction "PD5_64") (pintype "passive"))
    )
    (net (code "18") (name "/LCD_COM0") (class "Default")
      (node (ref "PG1") (pin "25") (pinfunction "25_25") (pintype "passive"))
      (node (ref "U6") (pin "41") (pinfunction "PA8_41") (pintype "passive"))
    )
    (net (code "19") (name "/LCD_COM1") (class "Default")
      (node (ref "PG1") (pin "24") (pinfunction "24_24") (pintype "passive"))
      (node (ref "U6") (pin "42") (pinfunction "PA9_42") (pintype "passive"))
    )
    (net (code "20") (name "/LCD_COM2") (class "Default")
      (node (ref "PG1") (pin "23") (pinfunction "23_23") (pintype "passive"))
      (node (ref "U6") (pin "43") (pinfunction "PA10_43") (pintype "passive"))
    )
    (net (code "21") (name "/LCD_COM3") (class "Default")
      (node (ref "PG1") (pin "22") (pinfunction "22_22") (pintype "passive"))
      (node (ref "U6") (pin "62") (pinfunction "PB9_62") (pintype "passive"))
    )
    (net (code "22") (name "/LCD_SEG5") (class "Default")
      (node (ref "PG1") (pin "21") (pinfunction "21_21") (pintype "passive"))
      (node (ref "U6") (pin "28") (pinfunction "PB0_28") (pintype "passive"))
    )
    (net (code "23") (name "/LCD_SEG6") (class "Default")
      (node (ref "PG1") (pin "20") (pinfunction "20_20") (pintype "passive"))
      (node (ref "U6") (pin "29") (pinfunction "PB1_29") (pintype "passive"))
    )
    (net (code "24") (name "/LCD_SEG10") (class "Default")
      (node (ref "PG1") (pin "19") (pinfunction "19_19") (pintype "passive"))
      (node (ref "U6") (pin "31") (pinfunction "PB10_31") (pintype "passive"))
    )
    (net (code "25") (name "/LCD_SEG11") (class "Default")
      (node (ref "PG1") (pin "18") (pinfunction "18_18") (pintype "passive"))
      (node (ref "U6") (pin "32") (pinfunction "PB11_32") (pintype "passive"))
    )
    (net (code "26") (name "/LCD_SEG12") (class "Default")
      (node (ref "PG1") (pin "17") (pinfunction "17_17") (pintype "passive"))
      (node (ref "U6") (pin "33") (pinfunction "PB12_33") (pintype "passive"))
    )
    (net (code "27") (name "/LCD_SEG13") (class "Default")
      (node (ref "PG1") (pin "16") (pinfunction "16_16") (pintype "passive"))
      (node (ref "U6") (pin "34") (pinfunction "PB13_34") (pintype "passive"))
    )
    (net (code "28") (name "/LCD_SEG14") (class "Default")
      (node (ref "PG1") (pin "15") (pinfunction "15_15") (pintype "passive"))
      (node (ref "U6") (pin "35") (pinfunction "PB14_35") (pintype "passive"))
    )
    (net (code "29") (name "/LCD_SEG15") (class "Default")
      (node (ref "PG1") (pin "14") (pinfunction "14_14") (pintype "passive"))
      (node (ref "U6") (pin "36") (pinfunction "PB15_36") (pintype "passive"))
    )
    (net (code "30") (name "/LCD_SEG24") (class "Default")
      (node (ref "PG1") (pin "13") (pinfunction "13_13") (pintype "passive"))
      (node (ref "U6") (pin "37") (pinfunction "PC6_37") (pintype "passive"))
    )
    (net (code "31") (name "/LCD_SEG25") (class "Default")
      (node (ref "PG1") (pin "12") (pinfunction "12_12") (pintype "passive"))
      (node (ref "U6") (pin "38") (pinfunction "PC7_38") (pintype "passive"))
    )
    (net (code "32") (name "/LCD_SEG26") (class "Default")
      (node (ref "PG1") (pin "11") (pinfunction "11_11") (pintype "passive"))
      (node (ref "U6") (pin "39") (pinfunction "PC8_39") (pintype "passive"))
    )
    (net (code "33") (name "/LCD_SEG27") (class "Default")
      (node (ref "PG1") (pin "10") (pinfunction "10_10") (pintype "passive"))
      (node (ref "U6") (pin "40") (pinfunction "PC9_40") (pintype "passive"))
    )
    (net (code "34") (name "/LCD_SEG28") (class "Default")
      (node (ref "PG1") (pin "9") (pinfunction "9_9") (pintype "passive"))
      (node (ref "U6") (pin "51") (pinfunction "PC10_51") (pintype "passive"))
    )
    (net (code "35") (name "/LCD_SEG29") (class "Default")
      (node (ref "PG1") (pin "8") (pinfunction "8_8") (pintype "passive"))
      (node (ref "U6") (pin "52") (pinfunction "PC11_52") (pintype "passive"))
    )
    (net (code "36") (name "/LCD_SEG30") (class "Default")
      (node (ref "PG1") (pin "7") (pinfunction "7_7") (pintype "passive"))
      (node (ref "U6") (pin "53") (pinfunction "PC12_53") (pintype "passive"))
    )
    (net (code "37") (name "/LCD_SEG31") (class "Default")
      (node (ref "PG1") (pin "6") (pinfunction "6_6") (pintype "passive"))
      (node (ref "U6") (pin "54") (pinfunction "PD2_54") (pintype "passive"))
    )
    (net (code "38") (name "/LED_ALM") (class "Default")
      (node (ref "R41") (pin "2") (pinfunction "2_2") (pintype "passive"))
      (node (ref "U6") (pin "27") (pinfunction "PC5/USART0_RX_27") (pintype "passive"))
    )
    (net (code "39") (name "/LED_NC1") (class "Default")
      (node (ref "R42") (pin "2") (pinfunction "2_2") (pintype "passive"))
      (node (ref "U6") (pin "12") (pinfunction "PC3_12") (pintype "passive"))
    )
    (net (code "40") (name "/LED_NC2") (class "Default")
      (node (ref "R43") (pin "2") (pinfunction "2_2") (pintype "passive"))
      (node (ref "U6") (pin "26") (pinfunction "PC4/USART0_TX_26") (pintype "passive"))
    )
    (net (code "41") (name "/LED_STA") (class "Default")
      (node (ref "R44") (pin "2") (pinfunction "2_2") (pintype "passive"))
      (node (ref "U6") (pin "11") (pinfunction "PC2_11") (pintype "passive"))
    )
    (net (code "42") (name "/MCU_BEEP") (class "Default")
      (node (ref "R55") (pin "2") (pinfunction "2_2") (pintype "passive"))
      (node (ref "U6") (pin "47") (pinfunction "PD0_47") (pintype "passive"))
    )
    (net (code "43") (name "/M_INT") (class "Default")
      (node (ref "U1") (pin "5") (pinfunction "INT1_5") (pintype "passive"))
      (node (ref "U6") (pin "48") (pinfunction "PD1_48") (pintype "passive"))
    )
    (net (code "44") (name "/NRST") (class "Default")
      (node (ref "C30") (pin "1") (pintype "passive"))
      (node (ref "J1") (pin "5") (pinfunction "5_5") (pintype "passive"))
      (node (ref "U6") (pin "8") (pinfunction "NRST_8") (pintype "passive"))
    )
    (net (code "45") (name "/PF0") (class "Default")
      (node (ref "R59") (pin "2") (pinfunction "2_2") (pintype "passive"))
      (node (ref "U6") (pin "6") (pinfunction "OSC_IN_6") (pintype "passive"))
    )
    (net (code "46") (name "/PF1") (class "Default")
      (node (ref "R26") (pin "2") (pinfunction "2_2") (pintype "passive"))
      (node (ref "U6") (pin "7") (pinfunction "OSC_OUT_7") (pintype "passive"))
    )
    (net (code "47") (name "/PGND") (class "Default")
      (node (ref "C1") (pin "1") (pintype "passive"))
      (node (ref "USB1") (pin "1") (pinfunction "1_1") (pintype "passive"))
      (node (ref "USB1") (pin "2") (pinfunction "2_2") (pintype "passive"))
      (node (ref "USB1") (pin "3") (pinfunction "3_3") (pintype "passive"))
      (node (ref "USB1") (pin "4") (pinfunction "4_4") (pintype "passive"))
    )
    (net (code "48") (name "/PT100_V-") (class "Default")
      (node (ref "J2") (pin "1") (pinfunction "1_1") (pintype "passive"))
      (node (ref "R12") (pin "2") (pinfunction "2_2") (pintype "passive"))
      (node (ref "R13") (pin "1") (pinfunction "1_1") (pintype "passive"))
      (node (ref "R61") (pin "1") (pinfunction "1_1") (pintype "passive"))
      (node (ref "R9") (pin "2") (pinfunction "2_2") (pintype "passive"))
    )
    (net (code "49") (name "/SPI0_MISO") (class "Default")
      (node (ref "U6") (pin "24") (pinfunction "PA6_24") (pintype "passive"))
      (node (ref "U9") (pin "2") (pinfunction "SO_2") (pintype "passive"))
    )
    (net (code "50") (name "/SPI0_MOSI") (class "Default")
      (node (ref "U6") (pin "25") (pinfunction "PA7_25") (pintype "passive"))
      (node (ref "U9") (pin "5") (pinfunction "SI_5") (pintype "passive"))
    )
    (net (code "51") (name "/SPI0_NSS") (class "Default")
      (node (ref "U6") (pin "22") (pinfunction "PA4/SPI0_NSS_22") (pintype "passive"))
      (node (ref "U9") (pin "1") (pinfunction "CS_1") (pintype "passive"))
    )
    (net (code "52") (name "/SPI0_SCK") (class "Default")
      (node (ref "U6") (pin "23") (pinfunction "PA5/SPI1_SCK_23") (pintype "passive"))
      (node (ref "U9") (pin "6") (pinfunction "CLK_6") (pintype "passive"))
    )
    (net (code "53") (name "/SPI1_MISO") (class "Default")
      (node (ref "U6") (pin "56") (pinfunction "PB4_56") (pintype "passive"))
      (node (ref "U8") (pin "2") (pinfunction "SO_2") (pintype "passive"))
    )
    (net (code "54") (name "/SPI1_MOSI") (class "Default")
      (node (ref "U6") (pin "57") (pinfunction "PB5_57") (pintype "passive"))
      (node (ref "U8") (pin "5") (pinfunction "SI_5") (pintype "passive"))
    )
    (net (code "55") (name "/SPI1_NSS") (class "Default")
      (node (ref "U6") (pin "50") (pinfunction "PA15_50") (pintype "passive"))
      (node (ref "U8") (pin "1") (pinfunction "CS_1") (pintype "passive"))
    )
    (net (code "56") (name "/SPI1_SCK") (class "Default")
      (node (ref "U6") (pin "55") (pinfunction "PB3_55") (pintype "passive"))
      (node (ref "U8") (pin "6") (pinfunction "CLK_6") (pintype "passive"))
    )
    (net (code "57") (name "/SW") (class "Default")
      (node (ref "L1") (pin "2") (pinfunction "2_2") (pintype "passive"))
      (node (ref "W2") (pin "1") (pinfunction "SW_1") (pintype "passive"))
    )
    (net (code "58") (name "/SWCLK") (class "Default")
      (node (ref "J1") (pin "2") (pinfunction "2_2") (pintype "passive"))
      (node (ref "U6") (pin "49") (pinfunction "PA14/SWCLK_49") (pintype "passive"))
    )
    (net (code "59") (name "/SWDIO") (class "Default")
      (node (ref "J1") (pin "3") (pinfunction "3_3") (pintype "passive"))
      (node (ref "U6") (pin "46") (pinfunction "PA13/SWDIO_46") (pintype "passive"))
    )
    (net (code "60") (name "/TH_PWR_EN") (class "Default")
      (node (ref "R10") (pin "1") (pinfunction "1_1") (pintype "passive"))
      (node (ref "U6") (pin "61") (pinfunction "PB8_61") (pintype "passive"))
    )
    (net (code "61") (name "/U1_RXD") (class "Default")
      (node (ref "J5") (pin "2") (pinfunction "2_2") (pintype "passive"))
      (node (ref "M1") (pin "2") (pinfunction "TXD1_2") (pintype "passive"))
      (node (ref "U6") (pin "19") (pinfunction "PA3_19") (pintype "passive"))
    )
    (net (code "62") (name "/U1_TXD") (class "Default")
      (node (ref "J5") (pin "3") (pinfunction "3_3") (pintype "passive"))
      (node (ref "M1") (pin "3") (pinfunction "RXD1_3") (pintype "passive"))
      (node (ref "U6") (pin "18") (pinfunction "PA2_18") (pintype "passive"))
    )
    (net (code "63") (name "/U3_RXD") (class "Default")
      (node (ref "U6") (pin "17") (pinfunction "PA1_17") (pintype "passive"))
    )
    (net (code "64") (name "/U3_TXD") (class "Default")
      (node (ref "U6") (pin "16") (pinfunction "PA0-WKUP_16") (pintype "passive"))
    )
    (net (code "65") (name "/USB_D+") (class "Default")
      (node (ref "D1") (pin "3") (pintype "passive"))
      (node (ref "L4") (pin "1") (pinfunction "1_1") (pintype "passive"))
      (node (ref "USB1") (pin "A6") (pinfunction "DP1_A6") (pintype "passive"))
      (node (ref "USB1") (pin "B6") (pinfunction "DP2_B6") (pintype "passive"))
    )
    (net (code "66") (name "/USB_D-") (class "Default")
      (node (ref "D1") (pin "2") (pintype "passive"))
      (node (ref "L4") (pin "3") (pinfunction "3_3") (pintype "passive"))
      (node (ref "USB1") (pin "A7") (pinfunction "DN1_A7") (pintype "passive"))
      (node (ref "USB1") (pin "B7") (pinfunction "DN2_B7") (pintype "passive"))
    )
    (net (code "67") (name "/USB_DM") (class "Default")
      (node (ref "L4") (pin "4") (pinfunction "4_4") (pintype "passive"))
      (node (ref "U6") (pin "44") (pinfunction "PA11/USB_DM_44") (pintype "passive"))
    )
    (net (code "68") (name "/USB_DP") (class "Default")
      (node (ref "L4") (pin "2") (pinfunction "2_2") (pintype "passive"))
      (node (ref "U6") (pin "45") (pinfunction "PA12/USB_DP_45") (pintype "passive"))
    )
    (net (code "69") (name "/USB_V+") (class "Default")
      (node (ref "D1") (pin "4") (pintype "passive"))
      (node (ref "L3") (pin "1") (pinfunction "1_1") (pintype "passive"))
      (node (ref "USB1") (pin "A4B9") (pinfunction "VBUS_A4B9") (pintype "passive"))
      (node (ref "USB1") (pin "B4A9") (pinfunction "VBUS_B4A9") (pintype "passive"))
    )
    (net (code "70") (name "/USB_V-") (class "Default")
      (node (ref "D1") (pin "1") (pintype "passive"))
      (node (ref "L2") (pin "1") (pinfunction "1_1") (pintype "passive"))
      (node (ref "USB1") (pin "A1B12") (pinfunction "GND_A1B12") (pintype "passive"))
      (node (ref "USB1") (pin "B1A12") (pinfunction "GND_B1A12") (pintype "passive"))
    )
    (net (code "71") (name "/USB_VOL") (class "Default")
      (node (ref "R19") (pin "1") (pinfunction "1_1") (pintype "passive"))
      (node (ref "R20") (pin "2") (pinfunction "2_2") (pintype "passive"))
      (node (ref "U6") (pin "9") (pinfunction "PC0/ADC_IN10_9") (pintype "passive"))
    )
    (net (code "72") (name "/V12_R") (class "Default")
      (node (ref "C15") (pin "1") (pintype "passive"))
      (node (ref "C9") (pin "2") (pintype "passive"))
      (node (ref "D2") (pin "4") (pintype "passive"))
      (node (ref "J2") (pin "4") (pinfunction "4_4") (pintype "passive"))
      (node (ref "R7") (pin "1") (pinfunction "1_1") (pintype "passive"))
      (node (ref "U5") (pin "8") (pinfunction "REFO_8") (pintype "passive"))
    )
    (net (code "73") (name "/VIN-T") (class "Default")
      (node (ref "C10") (pin "2") (pintype "passive"))
      (node (ref "C20") (pin "1") (pintype "passive"))
      (node (ref "C27") (pin "2") (pintype "passive"))
      (node (ref "C61") (pin "1") (pintype "passive"))
      (node (ref "D4") (pin "K") (pinfunction "K_K") (pintype "passive"))
      (node (ref "L5") (pin "1") (pinfunction "1_1") (pintype "passive"))
      (node (ref "Q2") (pin "2") (pinfunction "2_2") (pintype "passive"))
      (node (ref "R66") (pin "2") (pinfunction "2_2") (pintype "passive"))
      (node (ref "U13") (pin "6") (pinfunction "VIN_6") (pintype "passive"))
      (node (ref "U7") (pin "11") (pinfunction "VIN_11") (pintype "passive"))
      (node (ref "W2") (pin "7") (pinfunction "VIN_7") (pintype "passive"))
    )
    (net (code "74") (name "GND") (class "Default")
      (node (ref "C1") (pin "2") (pintype "passive"))
      (node (ref "C10") (pin "1") (pintype "passive"))
      (node (ref "C11") (pin "1") (pintype "passive"))
      (node (ref "C12") (pin "1") (pintype "passive"))
      (node (ref "C13") (pin "2") (pintype "passive"))
      (node (ref "C14") (pin "2") (pintype "passive"))
      (node (ref "C15") (pin "2") (pintype "passive"))
      (node (ref "C16") (pin "2") (pintype "passive"))
      (node (ref "C17") (pin "2") (pintype "passive"))
      (node (ref "C18") (pin "1") (pintype "passive"))
      (node (ref "C19") (pin "2") (pintype "passive"))
      (node (ref "C2") (pin "2") (pintype "passive"))
      (node (ref "C20") (pin "2") (pintype "passive"))
      (node (ref "C21") (pin "1") (pintype "passive"))
      (node (ref "C22") (pin "2") (pintype "passive"))
      (node (ref "C23") (pin "1") (pintype "passive"))
      (node (ref "C24") (pin "1") (pintype "passive"))
      (node (ref "C27") (pin "1") (pintype "passive"))
      (node (ref "C28") (pin "2") (pintype "passive"))
      (node (ref "C29") (pin "2") (pintype "passive"))
      (node (ref "C3") (pin "2") (pintype "passive"))
      (node (ref "C30") (pin "2") (pintype "passive"))
      (node (ref "C31") (pin "1") (pintype "passive"))
      (node (ref "C32") (pin "1") (pintype "passive"))
      (node (ref "C37") (pin "2") (pintype "passive"))
      (node (ref "C38") (pin "2") (pintype "passive"))
      (node (ref "C39") (pin "1") (pintype "passive"))
      (node (ref "C4") (pin "2") (pintype "passive"))
      (node (ref "C40") (pin "1") (pintype "passive"))
      (node (ref "C41") (pin "2") (pintype "passive"))
      (node (ref "C42") (pin "2") (pintype "passive"))
      (node (ref "C5") (pin "1") (pintype "passive"))
      (node (ref "C54") (pin "1") (pintype "passive"))
      (node (ref "C57") (pin "2") (pintype "passive"))
      (node (ref "C6") (pin "2") (pintype "passive"))
      (node (ref "C60") (pin "2") (pintype "passive"))
      (node (ref "C61") (pin "2") (pintype "passive"))
      (node (ref "C7") (pin "2") (pintype "passive"))
      (node (ref "C8") (pin "1") (pintype "passive"))
      (node (ref "C9") (pin "1") (pintype "passive"))
      (node (ref "D2") (pin "1") (pintype "passive"))
      (node (ref "H1") (pin "1") (pinfunction "1_1") (pintype "passive"))
      (node (ref "H2") (pin "1") (pinfunction "1_1") (pintype "passive"))
      (node (ref "H3") (pin "1") (pinfunction "1_1") (pintype "passive"))
      (node (ref "H4") (pin "1") (pinfunction "1_1") (pintype "passive"))
      (node (ref "H5") (pin "1") (pinfunction "1_1") (pintype "passive"))
      (node (ref "H6") (pin "1") (pinfunction "1_1") (pintype "passive"))
      (node (ref "J1") (pin "4") (pinfunction "4_4") (pintype "passive"))
      (node (ref "J2") (pin "5") (pinfunction "5_5") (pintype "passive"))
      (node (ref "J2") (pin "6") (pinfunction "6_6") (pintype "passive"))
      (node (ref "J3") (pin "1") (pinfunction "1_1") (pintype "passive"))
      (node (ref "J4") (pin "1") (pinfunction "1_1") (pintype "passive"))
      (node (ref "J5") (pin "1") (pinfunction "1_1") (pintype "passive"))
      (node (ref "K1") (pin "2") (pinfunction "2_2") (pintype "passive"))
      (node (ref "K2") (pin "2") (pinfunction "2_2") (pintype "passive"))
      (node (ref "L2") (pin "2") (pinfunction "2_2") (pintype "passive"))
      (node (ref "M1") (pin "1") (pinfunction "GND_1") (pintype "passive"))
      (node (ref "M1") (pin "10") (pinfunction "GND_10") (pintype "passive"))
      (node (ref "M1") (pin "12") (pinfunction "GND_12") (pintype "passive"))
      (node (ref "N1") (pin "1") (pinfunction "1_1") (pintype "passive"))
      (node (ref "Q8") (pin "E") (pinfunction "E_E") (pintype "passive"))
      (node (ref "R14") (pin "2") (pinfunction "2_2") (pintype "passive"))
      (node (ref "R17") (pin "1") (pinfunction "1_1") (pintype "passive"))
      (node (ref "R20") (pin "1") (pinfunction "1_1") (pintype "passive"))
      (node (ref "R21") (pin "1") (pinfunction "1_1") (pintype "passive"))
      (node (ref "R26") (pin "1") (pinfunction "1_1") (pintype "passive"))
      (node (ref "R30") (pin "1") (pinfunction "1_1") (pintype "passive"))
      (node (ref "R54") (pin "2") (pinfunction "2_2") (pintype "passive"))
      (node (ref "R59") (pin "1") (pinfunction "1_1") (pintype "passive"))
      (node (ref "R61") (pin "2") (pinfunction "2_2") (pintype "passive"))
      (node (ref "R65") (pin "2") (pinfunction "2_2") (pintype "passive"))
      (node (ref "R8") (pin "1") (pinfunction "1_1") (pintype "passive"))
      (node (ref "R9") (pin "1") (pinfunction "1_1") (pintype "passive"))
      (node (ref "U1") (pin "4") (pinfunction "NC_4") (pintype "passive"))
      (node (ref "U1") (pin "8") (pinfunction "GNDIO_8") (pintype "passive"))
      (node (ref "U1") (pin "9") (pinfunction "GND_9") (pintype "passive"))
      (node (ref "U12") (pin "C") (pinfunction "C_C") (pintype "passive"))
      (node (ref "U13") (pin "1") (pinfunction "GND_1") (pintype "passive"))
      (node (ref "U2") (pin "2") (pinfunction "GND_2") (pintype "passive"))
      (node (ref "U3") (pin "0") (pinfunction "Die_Pad_0") (pintype "passive"))
      (node (ref "U3") (pin "7") (pinfunction "R_7") (pintype "passive"))
      (node (ref "U3") (pin "8") (pinfunction "VSS_8") (pintype "passive"))
      (node (ref "U4") (pin "4") (pinfunction "VSS_4") (pintype "passive"))
      (node (ref "U5") (pin "2") (pinfunction "VSSA_2") (pintype "passive"))
      (node (ref "U6") (pin "13") (pinfunction "VSS_13") (pintype "passive"))
      (node (ref "U6") (pin "60") (pinfunction "PD3/BOOT0_60") (pintype "passive"))
      (node (ref "U7") (pin "2") (pinfunction "MODE/SYNC_2") (pintype "passive"))
      (node (ref "U7") (pin "5") (pinfunction "AGND_5") (pintype "passive"))
      (node (ref "U7") (pin "9") (pinfunction "PGND_9") (pintype "passive"))
      (node (ref "U8") (pin "4") (pinfunction "GND_4") (pintype "passive"))
      (node (ref "U9") (pin "4") (pinfunction "GND_4") (pintype "passive"))
      (node (ref "W1") (pin "2") (pinfunction "GND_2") (pintype "passive"))
      (node (ref "W2") (pin "0") (pinfunction "G_0") (pintype "passive"))
      (node (ref "W2") (pin "3") (pinfunction "CV_3") (pintype "passive"))
      (node (ref "W2") (pin "6") (pinfunction "NTC_6") (pintype "passive"))
      (node (ref "W2") (pin "8") (pinfunction "GND_8") (pintype "passive"))
      (node (ref "W3") (pin "2") (pinfunction "GND_2") (pintype "passive"))
      (node (ref "W4") (pin "2") (pinfunction "GND_2") (pintype "passive"))
    )
    (net (code "75") (name "GPS_3V3") (class "Default")
      (node (ref "C42") (pin "1") (pintype "passive"))
      (node (ref "M1") (pin "6") (pinfunction "V_BCKP_6") (pintype "passive"))
      (node (ref "M1") (pin "8") (pinfunction "VCC_8") (pintype "passive"))
      (node (ref "W4") (pin "5") (pinfunction "OUT_5") (pintype "passive"))
    )
    (net (code "76") (name "Net-(B1-Pad1)") (class "Default")
      (node (ref "B1") (pin "1") (pinfunction "1_1") (pintype "passive"))
      (node (ref "C54") (pin "2") (pintype "passive"))
      (node (ref "D11") (pin "K") (pinfunction "K_K") (pintype "passive"))
      (node (ref "R56") (pin "1") (pinfunction "1_1") (pintype "passive"))
    )
    (net (code "77") (name "Net-(B1-Pad2)") (class "Default")
      (node (ref "B1") (pin "2") (pinfunction "2_2") (pintype "passive"))
      (node (ref "D11") (pin "A") (pinfunction "A_A") (pintype "passive"))
      (node (ref "Q8") (pin "C") (pinfunction "C_C") (pintype "passive"))
    )
    (net (code "78") (name "Net-(D6->-Pad3)") (class "Default")
      (node (ref "D6") (pin "3") (pinfunction ">_3") (pintype "passive"))
      (node (ref "R41") (pin "1") (pinfunction "1_1") (pintype "passive"))
    )
    (net (code "79") (name "Net-(D6->-Pad4)") (class "Default")
      (node (ref "D6") (pin "4") (pinfunction ">_4") (pintype "passive"))
      (node (ref "R43") (pin "1") (pinfunction "1_1") (pintype "passive"))
    )
    (net (code "80") (name "Net-(D7->-Pad3)") (class "Default")
      (node (ref "D7") (pin "3") (pinfunction ">_3") (pintype "passive"))
      (node (ref "R42") (pin "1") (pinfunction "1_1") (pintype "passive"))
    )
    (net (code "81") (name "Net-(D7->-Pad4)") (class "Default")
      (node (ref "D7") (pin "4") (pinfunction ">_4") (pintype "passive"))
      (node (ref "R44") (pin "1") (pinfunction "1_1") (pintype "passive"))
    )
    (net (code "82") (name "Net-(L7-Pad1)") (class "Default")
      (node (ref "L7") (pin "1") (pinfunction "1_1") (pintype "passive"))
      (node (ref "R39") (pin "2") (pinfunction "2_2") (pintype "passive"))
    )
    (net (code "83") (name "Net-(M1-RF_IN)") (class "Default")
      (node (ref "C38") (pin "1") (pintype "passive"))
      (node (ref "C62") (pin "1") (pintype "passive"))
      (node (ref "M1") (pin "11") (pinfunction "RF_IN_11") (pintype "passive"))
    )
    (net (code "84") (name "Net-(Q1-Pad3)") (class "Default")
      (node (ref "Q1") (pin "3") (pinfunction "3_3") (pintype "passive"))
      (node (ref "Q2") (pin "3") (pinfunction "3_3") (pintype "passive"))
    )
    (net (code "85") (name "Net-(Q8-PadB)") (class "Default")
      (node (ref "Q8") (pin "B") (pinfunction "B_B") (pintype "passive"))
      (node (ref "R54") (pin "1") (pinfunction "1_1") (pintype "passive"))
      (node (ref "R55") (pin "1") (pinfunction "1_1") (pintype "passive"))
    )
    (net (code "86") (name "Net-(R28-Pad1)") (class "Default")
      (node (ref "R28") (pin "1") (pinfunction "1_1") (pintype "passive"))
      (node (ref "R29") (pin "2") (pinfunction "2_2") (pintype "passive"))
    )
    (net (code "87") (name "Net-(R64-Pad1)") (class "Default")
      (node (ref "R64") (pin "1") (pinfunction "1_1") (pintype "passive"))
      (node (ref "R65") (pin "1") (pinfunction "1_1") (pintype "passive"))
    )
    (net (code "88") (name "Net-(U2-DVI)") (class "Default")
      (node (ref "C57") (pin "1") (pintype "passive"))
      (node (ref "R2") (pin "2") (pinfunction "2_2") (pintype "passive"))
      (node (ref "U2") (pin "4") (pinfunction "DVI_4") (pintype "passive"))
    )
    (net (code "89") (name "Net-(U3-ADDR)") (class "Default")
      (node (ref "R62") (pin "1") (pinfunction "1_1") (pintype "passive"))
      (node (ref "U3") (pin "2") (pinfunction "ADDR_2") (pintype "passive"))
    )
    (net (code "90") (name "Net-(U5-AIN1)") (class "Default")
      (node (ref "R23") (pin "1") (pinfunction "1_1") (pintype "passive"))
      (node (ref "U5") (pin "4") (pinfunction "AIN1_4") (pintype "passive"))
    )
    (net (code "91") (name "Net-(U5-AIN2)") (class "Default")
      (node (ref "R18") (pin "1") (pinfunction "1_1") (pintype "passive"))
      (node (ref "U5") (pin "5") (pinfunction "AIN2_5") (pintype "passive"))
    )
    (net (code "92") (name "Net-(U5-AIN3)") (class "Default")
      (node (ref "R14") (pin "1") (pinfunction "1_1") (pintype "passive"))
      (node (ref "U5") (pin "6") (pinfunction "AIN3_6") (pintype "passive"))
    )
    (net (code "93") (name "Net-(U5-AIN4)") (class "Default")
      (node (ref "R12") (pin "1") (pinfunction "1_1") (pintype "passive"))
      (node (ref "U5") (pin "7") (pinfunction "AIN4_7") (pintype "passive"))
    )
    (net (code "94") (name "Net-(U5-REFN)") (class "Default")
      (node (ref "C58") (pin "1") (pintype "passive"))
      (node (ref "R8") (pin "2") (pinfunction "2_2") (pintype "passive"))
      (node (ref "U5") (pin "10") (pinfunction "REFN_10") (pintype "passive"))
    )
    (net (code "95") (name "Net-(U5-REFP)") (class "Default")
      (node (ref "C58") (pin "2") (pintype "passive"))
      (node (ref "R13") (pin "2") (pinfunction "2_2") (pintype "passive"))
      (node (ref "U5") (pin "9") (pinfunction "REFP_9") (pintype "passive"))
    )
    (net (code "96") (name "Net-(U5-VDDA)") (class "Default")
      (node (ref "C18") (pin "2") (pintype "passive"))
      (node (ref "U5") (pin "1") (pinfunction "VDDA_1") (pintype "passive"))
    )
    (net (code "97") (name "Net-(U6-PD6{slash}VSLCD)") (class "Default")
      (node (ref "C21") (pin "2") (pintype "passive"))
      (node (ref "R58") (pin "2") (pinfunction "2_2") (pintype "passive"))
      (node (ref "U6") (pin "1") (pinfunction "PD6/VSLCD_1") (pintype "passive"))
    )
    (net (code "98") (name "Net-(U7-EN)") (class "Default")
      (node (ref "R32") (pin "1") (pinfunction "1_1") (pintype "passive"))
      (node (ref "U7") (pin "1") (pinfunction "EN_1") (pintype "passive"))
    )
    (net (code "99") (name "Net-(U7-FB)") (class "Default")
      (node (ref "R29") (pin "1") (pinfunction "1_1") (pintype "passive"))
      (node (ref "R30") (pin "2") (pinfunction "2_2") (pintype "passive"))
      (node (ref "U7") (pin "6") (pinfunction "FB_6") (pintype "passive"))
    )
    (net (code "100") (name "Net-(U7-SW1)") (class "Default")
      (node (ref "L6") (pin "1") (pinfunction "1_1") (pintype "passive"))
      (node (ref "U7") (pin "10") (pinfunction "SW1_10") (pintype "passive"))
    )
    (net (code "101") (name "Net-(U7-SW2)") (class "Default")
      (node (ref "L6") (pin "2") (pinfunction "2_2") (pintype "passive"))
      (node (ref "U7") (pin "8") (pinfunction "SW2_8") (pintype "passive"))
    )
    (net (code "102") (name "Net-(U7-VCC)") (class "Default")
      (node (ref "C32") (pin "2") (pintype "passive"))
      (node (ref "U7") (pin "4") (pinfunction "VCC_4") (pintype "passive"))
    )
    (net (code "103") (name "Net-(U13-EN)") (class "Default")
      (node (ref "C60") (pin "1") (pintype "passive"))
      (node (ref "R66") (pin "1") (pinfunction "1_1") (pintype "passive"))
      (node (ref "U13") (pin "4") (pinfunction "EN_4") (pintype "passive"))
    )
    (net (code "104") (name "Net-(U13-FB)") (class "Default")
      (node (ref "C59") (pin "1") (pintype "passive"))
      (node (ref "R63") (pin "1") (pinfunction "1_1") (pintype "passive"))
      (node (ref "R64") (pin "2") (pinfunction "2_2") (pintype "passive"))
      (node (ref "U13") (pin "3") (pinfunction "FB_3") (pintype "passive"))
    )
    (net (code "105") (name "Net-(U13-SW)") (class "Default")
      (node (ref "L5") (pin "2") (pinfunction "2_2") (pintype "passive"))
      (node (ref "U13") (pin "5") (pinfunction "SW_5") (pintype "passive"))
    )
    (net (code "106") (name "Net-(W1-EN)") (class "Default")
      (node (ref "R10") (pin "2") (pinfunction "2_2") (pintype "passive"))
      (node (ref "W1") (pin "3") (pinfunction "EN_3") (pintype "passive"))
    )
    (net (code "107") (name "Net-(W2-CC)") (class "Default")
      (node (ref "R17") (pin "2") (pinfunction "2_2") (pintype "passive"))
      (node (ref "W2") (pin "4") (pinfunction "CC_4") (pintype "passive"))
    )
    (net (code "108") (name "Net-(W3-EN)") (class "Default")
      (node (ref "R11") (pin "2") (pinfunction "2_2") (pintype "passive"))
      (node (ref "W3") (pin "3") (pinfunction "EN_3") (pintype "passive"))
    )
    (net (code "109") (name "Net-(W4-EN)") (class "Default")
      (node (ref "R40") (pin "1") (pinfunction "1_1") (pintype "passive"))
      (node (ref "W4") (pin "3") (pinfunction "EN_3") (pintype "passive"))
    )
    (net (code "110") (name "USB_5V") (class "Default")
      (node (ref "C11") (pin "2") (pintype "passive"))
      (node (ref "C12") (pin "2") (pintype "passive"))
      (node (ref "D4") (pin "A") (pinfunction "A_A") (pintype "passive"))
      (node (ref "L3") (pin "2") (pinfunction "2_2") (pintype "passive"))
      (node (ref "Q1") (pin "1") (pinfunction "1_1") (pintype "passive"))
      (node (ref "Q2") (pin "1") (pinfunction "1_1") (pintype "passive"))
      (node (ref "R1") (pin "1") (pinfunction "1_1") (pintype "passive"))
      (node (ref "R19") (pin "2") (pinfunction "2_2") (pintype "passive"))
    )
    (net (code "111") (name "VCC_ADC") (class "Default")
      (node (ref "C16") (pin "1") (pintype "passive"))
      (node (ref "C3") (pin "1") (pintype "passive"))
      (node (ref "C6") (pin "1") (pintype "passive"))
      (node (ref "C7") (pin "1") (pintype "passive"))
      (node (ref "R15") (pin "1") (pinfunction "1_1") (pintype "passive"))
      (node (ref "R2") (pin "1") (pinfunction "1_1") (pintype "passive"))
      (node (ref "R3") (pin "2") (pinfunction "2_2") (pintype "passive"))
      (node (ref "R4") (pin "2") (pinfunction "2_2") (pintype "passive"))
      (node (ref "R62") (pin "2") (pinfunction "2_2") (pintype "passive"))
      (node (ref "R7") (pin "2") (pinfunction "2_2") (pintype "passive"))
      (node (ref "U12") (pin "B") (pinfunction "B_B") (pintype "passive"))
      (node (ref "U2") (pin "1") (pinfunction "VCC_1") (pintype "passive"))
      (node (ref "U3") (pin "5") (pinfunction "VDD_5") (pintype "passive"))
      (node (ref "U4") (pin "3") (pinfunction "VDD_3") (pintype "passive"))
      (node (ref "U5") (pin "16") (pinfunction "VDD_16") (pintype "passive"))
      (node (ref "W1") (pin "5") (pinfunction "OUT_5") (pintype "passive"))
    )
    (net (code "112") (name "VCC_BAT") (class "Default")
      (node (ref "C8") (pin "2") (pintype "passive"))
      (node (ref "J3") (pin "2") (pinfunction "2_2") (pintype "passive"))
      (node (ref "J4") (pin "2") (pinfunction "2_2") (pintype "passive"))
      (node (ref "L1") (pin "1") (pinfunction "1_1") (pintype "passive"))
      (node (ref "Q1") (pin "2") (pinfunction "2_2") (pintype "passive"))
      (node (ref "R22") (pin "2") (pinfunction "2_2") (pintype "passive"))
      (node (ref "W2") (pin "5") (pinfunction "VBAT_5") (pintype "passive"))
    )
    (net (code "113") (name "VCC_LTE") (class "Default")
      (node (ref "C28") (pin "1") (pintype "passive"))
      (node (ref "C29") (pin "1") (pintype "passive"))
      (node (ref "C31") (pin "2") (pintype "passive"))
      (node (ref "R28") (pin "2") (pinfunction "2_2") (pintype "passive"))
      (node (ref "U7") (pin "7") (pinfunction "VOUT_7") (pintype "passive"))
    )
    (net (code "114") (name "VCC_MCU") (class "Default")
      (node (ref "C13") (pin "1") (pintype "passive"))
      (node (ref "C19") (pin "1") (pintype "passive"))
      (node (ref "C22") (pin "1") (pintype "passive"))
      (node (ref "C41") (pin "1") (pintype "passive"))
      (node (ref "D6") (pin "1") (pinfunction ">_1") (pintype "passive"))
      (node (ref "D6") (pin "2") (pinfunction ">_2") (pintype "passive"))
      (node (ref "D7") (pin "1") (pinfunction ">_1") (pintype "passive"))
      (node (ref "D7") (pin "2") (pinfunction ">_2") (pintype "passive"))
      (node (ref "J1") (pin "1") (pinfunction "1_1") (pintype "passive"))
      (node (ref "R16") (pin "1") (pinfunction "1_1") (pintype "passive"))
      (node (ref "R58") (pin "1") (pinfunction "1_1") (pintype "passive"))
      (node (ref "U6") (pin "14") (pinfunction "VREFP_14") (pintype "passive"))
      (node (ref "U6") (pin "15") (pinfunction "VDD_15") (pintype "passive"))
      (node (ref "U6") (pin "2") (pinfunction "VBAT_2") (pintype "passive"))
      (node (ref "U8") (pin "3") (pinfunction "WP#_3") (pintype "passive"))
      (node (ref "U8") (pin "7") (pinfunction "HOLD_7") (pintype "passive"))
      (node (ref "U8") (pin "8") (pinfunction "VCC_8") (pintype "passive"))
      (node (ref "U9") (pin "3") (pinfunction "WP#_3") (pintype "passive"))
      (node (ref "U9") (pin "7") (pinfunction "HOLD_7") (pintype "passive"))
      (node (ref "U9") (pin "8") (pinfunction "VCC_8") (pintype "passive"))
      (node (ref "W3") (pin "5") (pinfunction "OUT_5") (pintype "passive"))
    )
    (net (code "115") (name "VCC_SC") (class "Default")
      (node (ref "C2") (pin "1") (pintype "passive"))
      (node (ref "R15") (pin "2") (pinfunction "2_2") (pintype "passive"))
      (node (ref "R16") (pin "2") (pinfunction "2_2") (pintype "passive"))
      (node (ref "U1") (pin "1") (pinfunction "SDO_1") (pintype "passive"))
      (node (ref "U1") (pin "3") (pinfunction "VDDIO_3") (pintype "passive"))
      (node (ref "U1") (pin "7") (pinfunction "VDD_7") (pintype "passive"))
    )
    (net (code "116") (name "VCC_SYS") (class "Default")
      (node (ref "C14") (pin "1") (pintype "passive"))
      (node (ref "C59") (pin "2") (pintype "passive"))
      (node (ref "R11") (pin "1") (pinfunction "1_1") (pintype "passive"))
      (node (ref "R56") (pin "2") (pinfunction "2_2") (pintype "passive"))
      (node (ref "R63") (pin "2") (pinfunction "2_2") (pintype "passive"))
      (node (ref "U13") (pin "2") (pinfunction "VOUT_2") (pintype "passive"))
      (node (ref "W1") (pin "1") (pinfunction "IN_1") (pintype "passive"))
      (node (ref "W3") (pin "1") (pinfunction "IN_1") (pintype "passive"))
      (node (ref "W4") (pin "1") (pinfunction "IN_1") (pintype "passive"))
    )
    (net (code "117") (name "unconnected-(LCD1-Pad1)") (class "Default")
      (node (ref "LCD1") (pin "1") (pinfunction "1_1") (pintype "passive"))
    )
    (net (code "118") (name "unconnected-(M1-1PPS-Pad4)") (class "Default")
      (node (ref "M1") (pin "4") (pinfunction "1PPS_4") (pintype "passive"))
    )
    (net (code "119") (name "unconnected-(M1-ANTON-Pad13)") (class "Default")
      (node (ref "M1") (pin "13") (pinfunction "ANTON_13") (pintype "passive"))
    )
    (net (code "120") (name "unconnected-(M1-FORCE_ON-Pad18)") (class "Default")
      (node (ref "M1") (pin "18") (pinfunction "FORCE_ON_18") (pintype "passive"))
    )
    (net (code "121") (name "unconnected-(M1-NC-Pad7)") (class "Default")
      (node (ref "M1") (pin "7") (pinfunction "NC_7") (pintype "passive"))
    )
    (net (code "122") (name "unconnected-(M1-NC-Pad15)") (class "Default")
      (node (ref "M1") (pin "15") (pinfunction "NC_15") (pintype "passive"))
    )
    (net (code "123") (name "unconnected-(M1-RESERVED-Pad16)") (class "Default")
      (node (ref "M1") (pin "16") (pinfunction "RESERVED_16") (pintype "passive"))
    )
    (net (code "124") (name "unconnected-(M1-RESERVED-Pad17)") (class "Default")
      (node (ref "M1") (pin "17") (pinfunction "RESERVED_17") (pintype "passive"))
    )
    (net (code "125") (name "unconnected-(M1-RESET-Pad9)") (class "Default")
      (node (ref "M1") (pin "9") (pinfunction "RESET_9") (pintype "passive"))
    )
    (net (code "126") (name "unconnected-(M1-STANDBY-Pad5)") (class "Default")
      (node (ref "M1") (pin "5") (pinfunction "STANDBY_5") (pintype "passive"))
    )
    (net (code "127") (name "unconnected-(PG1-Pad1)") (class "Default")
      (node (ref "PG1") (pin "1") (pinfunction "1_1") (pintype "passive"))
    )
    (net (code "128") (name "unconnected-(PG1-Pad2)") (class "Default")
      (node (ref "PG1") (pin "2") (pinfunction "2_2") (pintype "passive"))
    )
    (net (code "129") (name "unconnected-(PG1-Pad3)") (class "Default")
      (node (ref "PG1") (pin "3") (pinfunction "3_3") (pintype "passive"))
    )
    (net (code "130") (name "unconnected-(PG1-Pad4)") (class "Default")
      (node (ref "PG1") (pin "4") (pinfunction "4_4") (pintype "passive"))
    )
    (net (code "131") (name "unconnected-(PG1-Pad5)") (class "Default")
      (node (ref "PG1") (pin "5") (pinfunction "5_5") (pintype "passive"))
    )
    (net (code "132") (name "unconnected-(U1-CS-Pad10)") (class "Default")
      (node (ref "U1") (pin "10") (pinfunction "CS_10") (pintype "passive"))
    )
    (net (code "133") (name "unconnected-(U1-INT2-Pad6)") (class "Default")
      (node (ref "U1") (pin "6") (pinfunction "INT2_6") (pintype "passive"))
    )
    (net (code "134") (name "unconnected-(U1-NC-Pad11)") (class "Default")
      (node (ref "U1") (pin "11") (pinfunction "NC_11") (pintype "passive"))
    )
    (net (code "135") (name "unconnected-(U3-ALERT-Pad3)") (class "Default")
      (node (ref "U3") (pin "3") (pinfunction "ALERT_3") (pintype "passive"))
    )
    (net (code "136") (name "unconnected-(U3-nRESET-Pad6)") (class "Default")
      (node (ref "U3") (pin "6") (pinfunction "nRESET_6") (pintype "passive"))
    )
    (net (code "137") (name "unconnected-(U5-CKIN-Pad12)") (class "Default")
      (node (ref "U5") (pin "12") (pinfunction "CKIN_12") (pintype "passive"))
    )
    (net (code "138") (name "unconnected-(U5-CKOUT-Pad13)") (class "Default")
      (node (ref "U5") (pin "13") (pinfunction "CKOUT_13") (pintype "passive"))
    )
    (net (code "139") (name "unconnected-(U5-OPO-Pad3)") (class "Default")
      (node (ref "U5") (pin "3") (pinfunction "OPO_3") (pintype "passive"))
    )
    (net (code "140") (name "unconnected-(U5-VSS-Pad11)") (class "Default")
      (node (ref "U5") (pin "11") (pinfunction "VSS_11") (pintype "passive"))
    )
    (net (code "141") (name "unconnected-(U7-PG-Pad3)") (class "Default")
      (node (ref "U7") (pin "3") (pinfunction "PG_3") (pintype "passive"))
    )
    (net (code "142") (name "unconnected-(USB1-CC2-PadB5)") (class "Default")
      (node (ref "USB1") (pin "B5") (pinfunction "CC2_B5") (pintype "passive"))
    )
    (net (code "143") (name "unconnected-(USB1-SBU2-PadB8)") (class "Default")
      (node (ref "USB1") (pin "B8") (pinfunction "SBU2_B8") (pintype "passive"))
    )
    (net (code "144") (name "unconnected-(W1-NC-Pad4)") (class "Default")
      (node (ref "W1") (pin "4") (pinfunction "NC_4") (pintype "passive"))
    )
    (net (code "145") (name "unconnected-(W3-NC-Pad4)") (class "Default")
      (node (ref "W3") (pin "4") (pinfunction "NC_4") (pintype "passive"))
    )
    (net (code "146") (name "unconnected-(W4-NC-Pad4)") (class "Default")
      (node (ref "W4") (pin "4") (pinfunction "NC_4") (pintype "passive"))
    )
  )
)
